# Homework_1.net
KiCad netlist of a schematic drawn in EasyEDA Pro
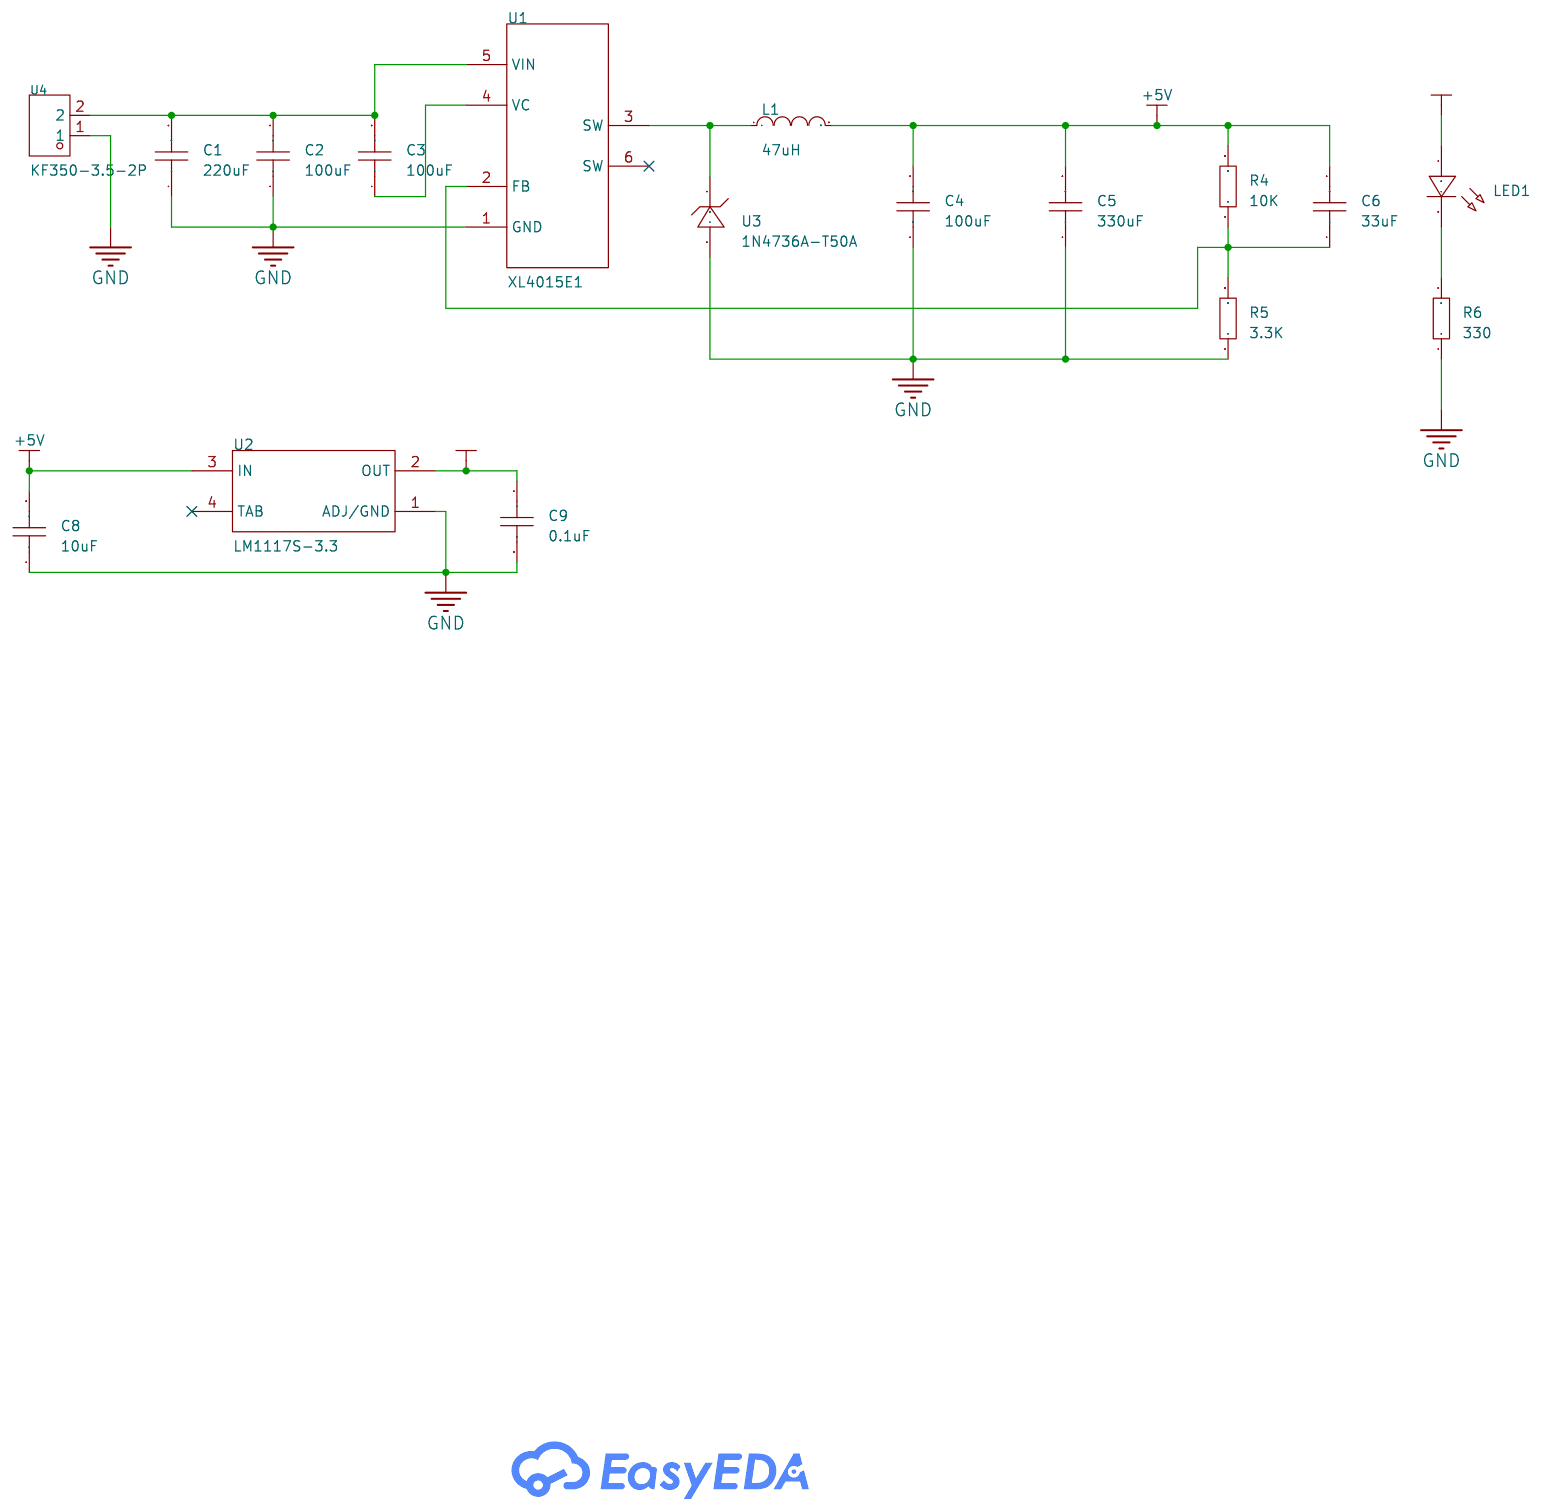
[diagram p0: Nguồn]
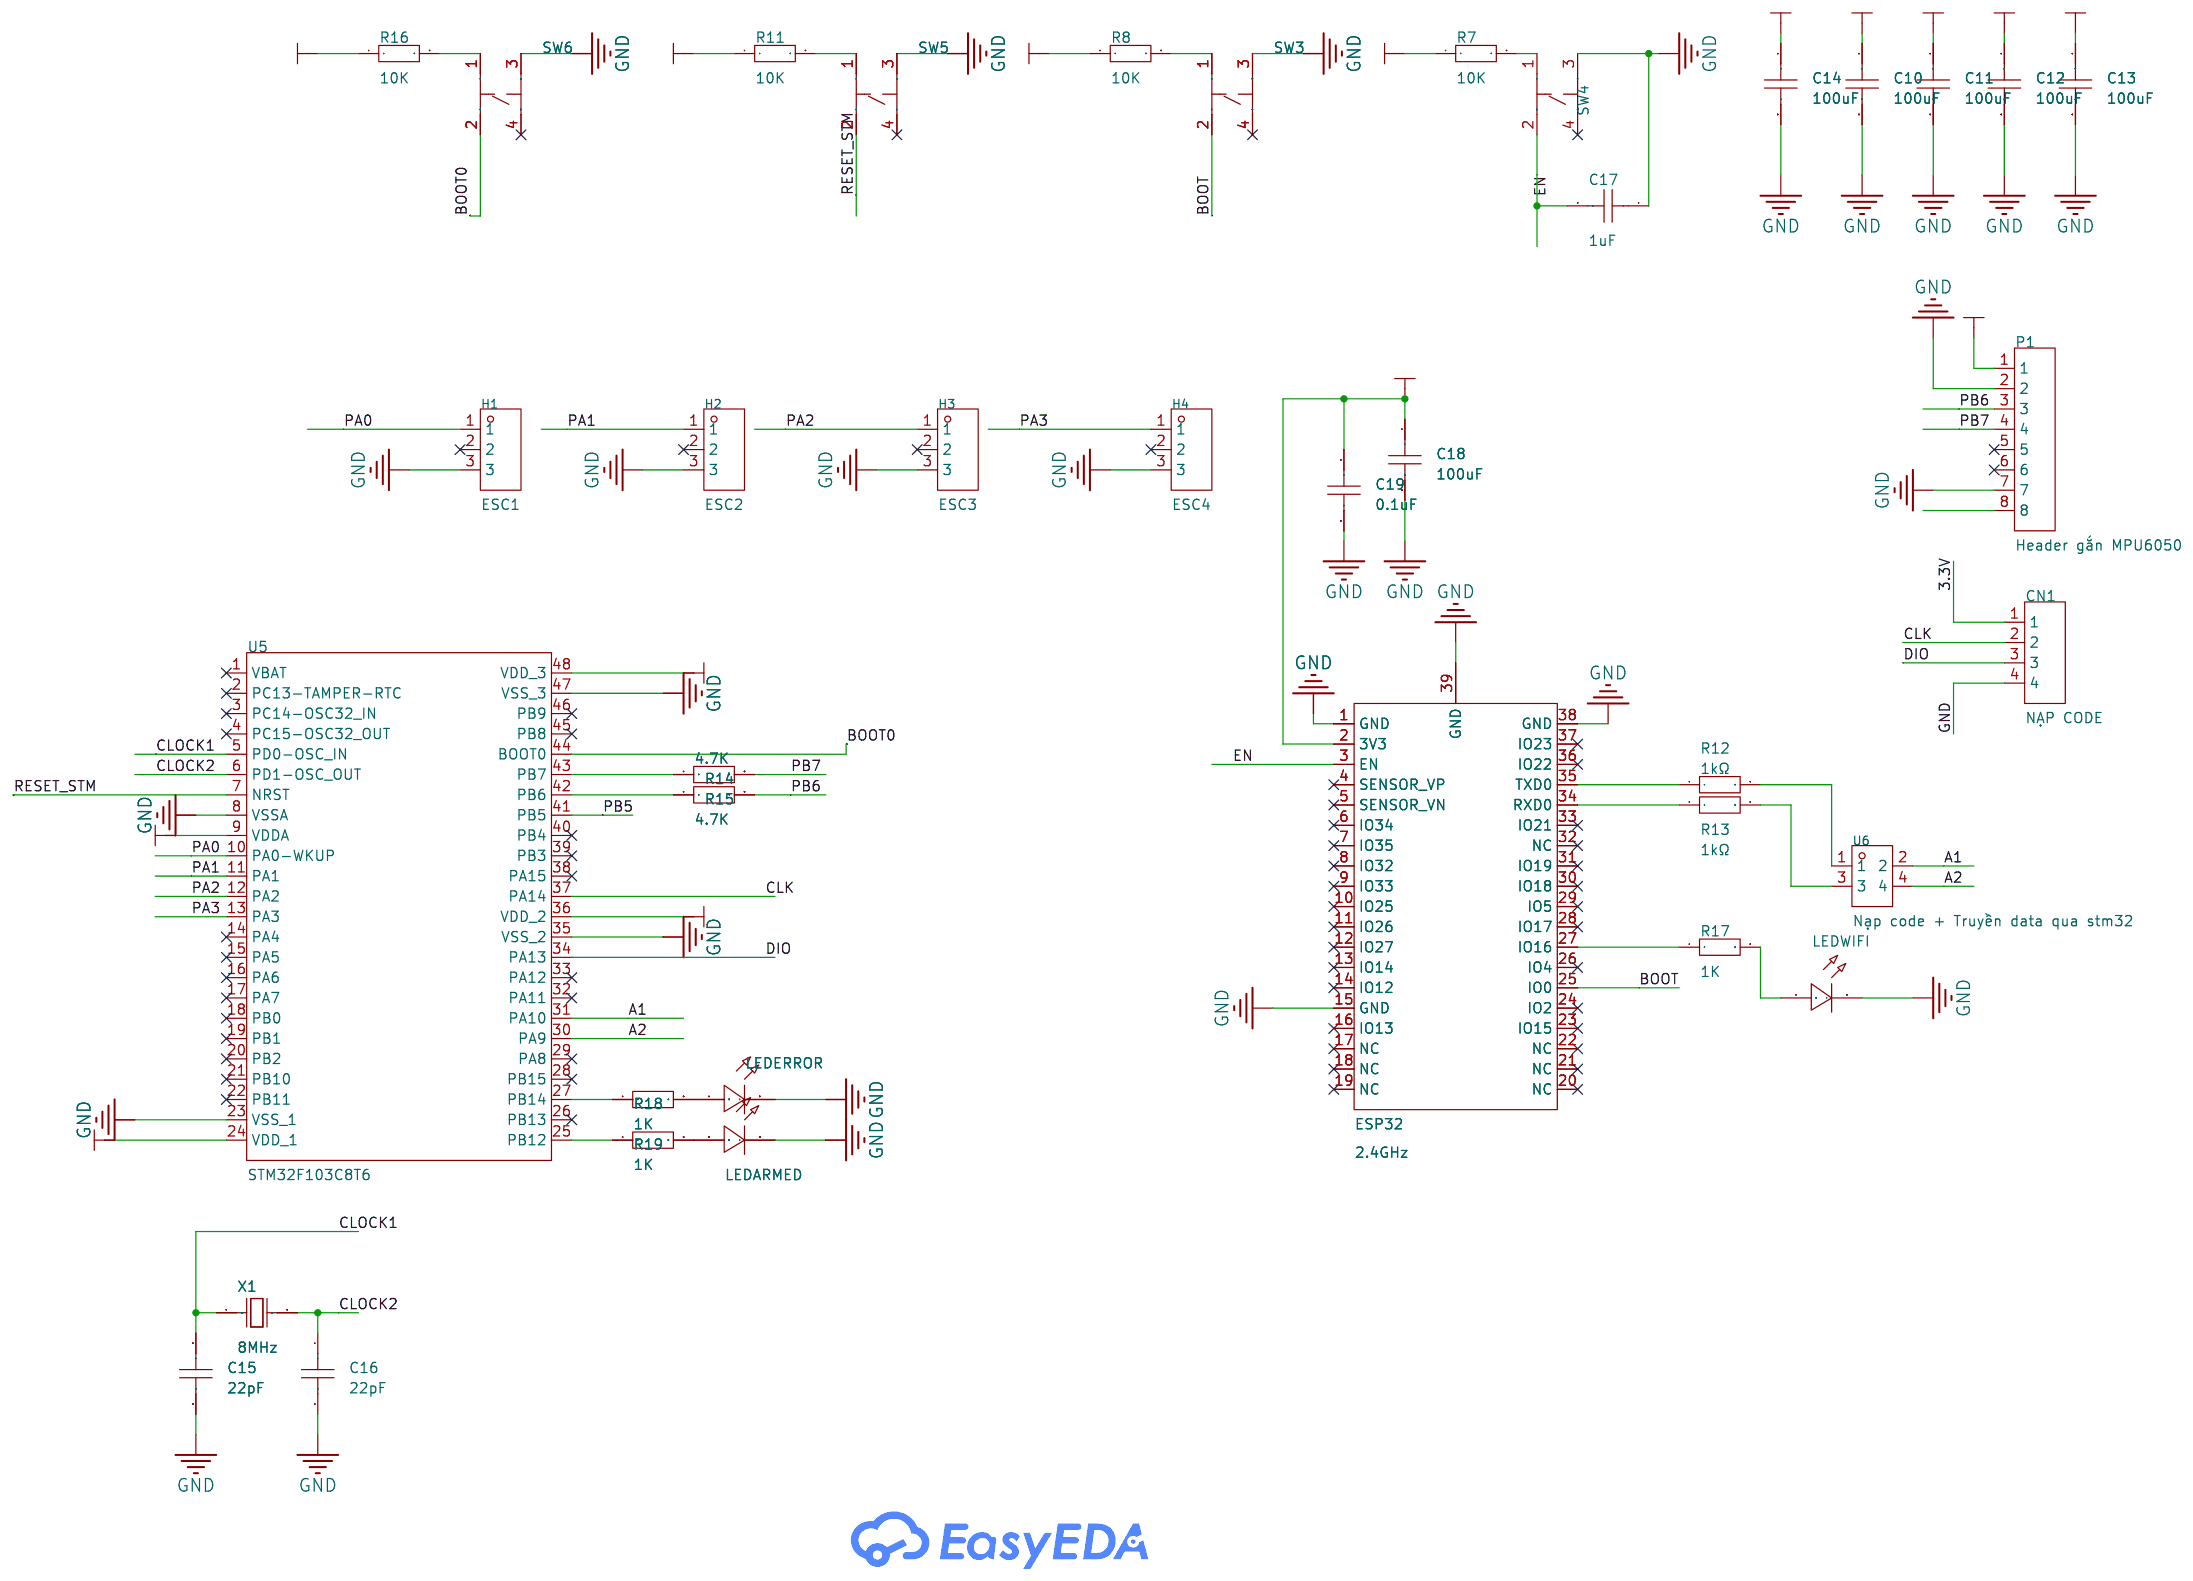
[diagram p1: Não]

(export (version "E")
  (design (tool "Eeschema 10.0.6"))
  (components
    (comp (ref "C1")
      (value "220uF")
      (footprint "easyedapro:C0805")
      (libsource (lib "easyedapro") (part "CAP"))
    )
    (comp (ref "C2")
      (value "100uF")
      (footprint "easyedapro:C0805")
      (libsource (lib "easyedapro") (part "CAP"))
    )
    (comp (ref "C3")
      (value "100uF")
      (footprint "easyedapro:C0805")
      (libsource (lib "easyedapro") (part "CAP"))
    )
    (comp (ref "C4")
      (value "100uF")
      (footprint "easyedapro:C0805")
      (libsource (lib "easyedapro") (part "CAP"))
    )
    (comp (ref "C5")
      (value "330uF")
      (footprint "easyedapro:C0805")
      (libsource (lib "easyedapro") (part "CAP"))
    )
    (comp (ref "C6")
      (value "33uF")
      (footprint "easyedapro:C0805")
      (libsource (lib "easyedapro") (part "CAP"))
    )
    (comp (ref "C8")
      (value "10uF")
      (footprint "easyedapro:C0805")
      (libsource (lib "easyedapro") (part "CAP"))
    )
    (comp (ref "C9")
      (value "0.1uF")
      (footprint "easyedapro:C0805")
      (libsource (lib "easyedapro") (part "CAP"))
    )
    (comp (ref "L1") (value "47uH") (footprint "easyedapro:L0603") (libsource (lib "easyedapro") (part "电感")))
    (comp (ref "LED1")
      (value "~")
      (footprint "easyedapro:LED-TH_BD5.8-P2.54-FD")
      (libsource (lib "easyedapro") (part "LED_TH-R"))
    )
    (comp (ref "R4")
      (value "10K")
      (footprint "easyedapro:R_AXIAL-0.4")
      (libsource (lib "easyedapro") (part "Res"))
    )
    (comp (ref "R5")
      (value "3.3K")
      (footprint "easyedapro:R_AXIAL-0.4")
      (libsource (lib "easyedapro") (part "Res"))
    )
    (comp (ref "R6")
      (value "330")
      (footprint "easyedapro:R_AXIAL-0.4")
      (libsource (lib "easyedapro") (part "Res"))
    )
    (comp (ref "U1")
      (value "XL4015E1")
      (footprint "easyedapro:TO-263-5_L10.2-W8.9-P1.70-TL")
      (fields (field (name "Manufacturer") "XLSEMI(芯龙)"))
      (libsource (lib "easyedapro") (part "XL4015E1"))
    )
    (comp (ref "U2")
      (value "LM1117S-3.3")
      (footprint "easyedapro:SOT-223-3_L6.5-W3.4-P2.30-LS7.0-BR")
      (fields (field (name "Manufacturer") "HTC"))
      (libsource (lib "easyedapro") (part "LM1117S-3.3"))
    )
    (comp (ref "U3")
      (value "1N4736A-T50A")
      (footprint "easyedapro:DO-41_BD2.4-L4.7-P8.70-D0.9-RD")
      (fields (field (name "Manufacturer") "onsemi(安森美)"))
      (libsource (lib "easyedapro") (part "1N4736A-T50A"))
    )
    (comp (ref "U4")
      (value "KF350-3.5-2P")
      (footprint "easyedapro:CONN-TH_P3.50_KF350-3.5-2P")
      (fields (field (name "Manufacturer") "KEFA(科发)"))
      (libsource (lib "easyedapro") (part "KF350-3.5-2P"))
    )
    (comp (ref "C10")
      (value "100uF")
      (footprint "easyedapro:C0805")
      (libsource (lib "easyedapro") (part "CAP"))
    )
    (comp (ref "C11")
      (value "100uF")
      (footprint "easyedapro:C0805")
      (libsource (lib "easyedapro") (part "CAP"))
    )
    (comp (ref "C12")
      (value "100uF")
      (footprint "easyedapro:C0805")
      (libsource (lib "easyedapro") (part "CAP"))
    )
    (comp (ref "C13")
      (value "100uF")
      (footprint "easyedapro:C0805")
      (libsource (lib "easyedapro") (part "CAP"))
    )
    (comp (ref "C14")
      (value "100uF")
      (footprint "easyedapro:C0805")
      (libsource (lib "easyedapro") (part "CAP"))
    )
    (comp (ref "C15")
      (value "22pF")
      (footprint "easyedapro:C0805")
      (libsource (lib "easyedapro") (part "CAP"))
    )
    (comp (ref "C16")
      (value "22pF")
      (footprint "easyedapro:C0805")
      (libsource (lib "easyedapro") (part "CAP"))
    )
    (comp (ref "C17")
      (value "1uF")
      (footprint "easyedapro:C0805")
      (libsource (lib "easyedapro") (part "CAP"))
    )
    (comp (ref "C18")
      (value "100uF")
      (footprint "easyedapro:C0805")
      (libsource (lib "easyedapro") (part "CAP"))
    )
    (comp (ref "C19")
      (value "0.1uF")
      (footprint "easyedapro:C0805")
      (libsource (lib "easyedapro") (part "CAP"))
    )
    (comp (ref "CN1")
      (value "NẠP CODE")
      (footprint "easyedapro:CONN-TH_XY-XH2.54-4A11-YT")
      (fields (field (name "Manufacturer") "HC(虹成电子)"))
      (libsource (lib "easyedapro") (part "HC-XH2.54-4A-M"))
    )
    (comp (ref "ESP32")
      (value "2.4GHz")
      (footprint "easyedapro:WIFI-SMD_ESP32-WROOM-32E")
      (fields
        (field (name "Manufacturer Part") "ESP32-WROOM-32E-N4")
        (field (name "Manufacturer") "ESPRESSIF(乐鑫)")
      )
      (libsource (lib "easyedapro") (part "ESP32-WROOM-32E(4MB)"))
    )
    (comp (ref "H1")
      (value "ESC1")
      (footprint "easyedapro:HDR-TH_3P-P2.54-V-M-1")
      (fields (field (name "Manufacturer") "ZHOURI(洲日)"))
      (libsource (lib "easyedapro") (part "2.54-1*3"))
    )
    (comp (ref "H2")
      (value "ESC2")
      (footprint "easyedapro:HDR-TH_3P-P2.54-V-M-1")
      (fields (field (name "Manufacturer") "ZHOURI(洲日)"))
      (libsource (lib "easyedapro") (part "2.54-1*3"))
    )
    (comp (ref "H3")
      (value "ESC3")
      (footprint "easyedapro:HDR-TH_3P-P2.54-V-M-1")
      (fields (field (name "Manufacturer") "ZHOURI(洲日)"))
      (libsource (lib "easyedapro") (part "2.54-1*3"))
    )
    (comp (ref "H4")
      (value "ESC4")
      (footprint "easyedapro:HDR-TH_3P-P2.54-V-M-1")
      (fields (field (name "Manufacturer") "ZHOURI(洲日)"))
      (libsource (lib "easyedapro") (part "2.54-1*3"))
    )
    (comp (ref "LEDARMED")
      (value "~")
      (footprint "easyedapro:LED-TH_BD5.8-P2.54-FD")
      (libsource (lib "easyedapro") (part "LED_TH-R"))
    )
    (comp (ref "LEDERROR")
      (value "~")
      (footprint "easyedapro:LED-TH_BD5.8-P2.54-FD")
      (libsource (lib "easyedapro") (part "LED_TH-R"))
    )
    (comp (ref "LEDWIFI")
      (value "~")
      (footprint "easyedapro:LED-TH_BD5.8-P2.54-FD")
      (libsource (lib "easyedapro") (part "LED_TH-R"))
    )
    (comp (ref "P1")
      (value "Header gắn MPU6050")
      (footprint "easyedapro:HDR-TH_8P-P2.54-V-F")
      (fields (field (name "Manufacturer") "BOOMELE(博穆精密)"))
      (libsource (lib "easyedapro") (part "Header-Female-2.54_1x8"))
    )
    (comp (ref "R7")
      (value "10K")
      (footprint "easyedapro:R_AXIAL-0.4")
      (libsource (lib "easyedapro") (part "Res"))
    )
    (comp (ref "R8")
      (value "10K")
      (footprint "easyedapro:R_AXIAL-0.4")
      (libsource (lib "easyedapro") (part "Res"))
    )
    (comp (ref "R11")
      (value "10K")
      (footprint "easyedapro:R_AXIAL-0.4")
      (libsource (lib "easyedapro") (part "Res"))
    )
    (comp (ref "R12")
      (value "1kΩ")
      (footprint "easyedapro:R_AXIAL-0.4")
      (libsource (lib "easyedapro") (part "Res"))
    )
    (comp (ref "R13")
      (value "1kΩ")
      (footprint "easyedapro:R_AXIAL-0.4")
      (libsource (lib "easyedapro") (part "Res"))
    )
    (comp (ref "R14")
      (value "4.7K")
      (footprint "easyedapro:R_AXIAL-0.4")
      (libsource (lib "easyedapro") (part "Res"))
    )
    (comp (ref "R15")
      (value "4.7K")
      (footprint "easyedapro:R_AXIAL-0.4")
      (libsource (lib "easyedapro") (part "Res"))
    )
    (comp (ref "R16")
      (value "10K")
      (footprint "easyedapro:R_AXIAL-0.4")
      (libsource (lib "easyedapro") (part "Res"))
    )
    (comp (ref "R17")
      (value "1K")
      (footprint "easyedapro:R_AXIAL-0.4")
      (libsource (lib "easyedapro") (part "Res"))
    )
    (comp (ref "R18")
      (value "1K")
      (footprint "easyedapro:R_AXIAL-0.4")
      (libsource (lib "easyedapro") (part "Res"))
    )
    (comp (ref "R19")
      (value "1K")
      (footprint "easyedapro:R_AXIAL-0.4")
      (libsource (lib "easyedapro") (part "Res"))
    )
    (comp (ref "SW3")
      (value "BOOT")
      (footprint "easyedapro:SW-SMD_4P-L6.0-W6.0-P4.50-LS9.0-H7.3")
      (fields (field (name "Manufacturer") "hanxia(韩下)"))
      (libsource (lib "easyedapro") (part "HX-6X6X7.3-TP FT SQUARE BUTTON"))
    )
    (comp (ref "SW4")
      (value "SW")
      (footprint "easyedapro:SW-SMD_4P-L6.0-W6.0-P4.50-LS9.0-H7.3")
      (fields (field (name "Manufacturer") "hanxia(韩下)"))
      (libsource (lib "easyedapro") (part "HX-6X6X7.3-TP FT SQUARE BUTTON"))
    )
    (comp (ref "SW5")
      (value "BOOT")
      (footprint "easyedapro:SW-SMD_4P-L6.0-W6.0-P4.50-LS9.0-H7.3")
      (fields (field (name "Manufacturer") "hanxia(韩下)"))
      (libsource (lib "easyedapro") (part "HX-6X6X7.3-TP FT SQUARE BUTTON"))
    )
    (comp (ref "SW6")
      (value "BOOT")
      (footprint "easyedapro:SW-SMD_4P-L6.0-W6.0-P4.50-LS9.0-H7.3")
      (fields (field (name "Manufacturer") "hanxia(韩下)"))
      (libsource (lib "easyedapro") (part "HX-6X6X7.3-TP FT SQUARE BUTTON"))
    )
    (comp (ref "U5")
      (value "STM32F103C8T6")
      (footprint "easyedapro:LQFP-48_L7.0-W7.0-P0.50-LS9.0-BL")
      (fields (field (name "Manufacturer") "ST(意法半导体)"))
      (libsource (lib "easyedapro") (part "STM32F103C8T6"))
    )
    (comp (ref "U6")
      (value "Nạp code + Truyền data qua stm32")
      (footprint "easyedapro:HDR-TH_4P-P2.54-V-M-R2-C2-S2.54")
      (fields (field (name "Manufacturer") "ZHOURI(洲日)"))
      (libsource (lib "easyedapro") (part "PZ2.54-2*2"))
    )
    (comp (ref "X1")
      (value "8MHz")
      (footprint "easyedapro:HC-49S_L11.0-W4.7-P4.88")
      (fields
        (field (name "Manufacturer Part") "049ST2-8.000F16HPNLL")
        (field (name "Manufacturer") "HCI(杭晶)")
      )
      (libsource (lib "easyedapro") (part "049ST2-8.000F16HPNLL"))
    )
  )
  (nets
    (net (code "1") (name "+5V") (class "Default")
      (node (ref "C4") (pin "2") (pinfunction "2_2") (pintype "input"))
      (node (ref "C5") (pin "2") (pinfunction "2_2") (pintype "input"))
      (node (ref "C6") (pin "2") (pinfunction "2_2") (pintype "input"))
      (node (ref "C8") (pin "2") (pinfunction "2_2") (pintype "input"))
      (node (ref "L1") (pin "2") (pinfunction "2_2") (pintype "input"))
      (node (ref "R4") (pin "2") (pinfunction "2_2") (pintype "input"))
      (node (ref "U2") (pin "3") (pinfunction "IN_3") (pintype "unspecified"))
    )
    (net (code "2") (name "3.3V") (class "Default")
      (node (ref "C10") (pin "1") (pinfunction "1_1") (pintype "input"))
      (node (ref "C11") (pin "1") (pinfunction "1_1") (pintype "input"))
      (node (ref "C12") (pin "1") (pinfunction "1_1") (pintype "input"))
      (node (ref "C13") (pin "1") (pinfunction "1_1") (pintype "input"))
      (node (ref "C14") (pin "1") (pinfunction "1_1") (pintype "input"))
      (node (ref "C18") (pin "1") (pinfunction "1_1") (pintype "input"))
      (node (ref "C19") (pin "1") (pinfunction "1_1") (pintype "input"))
      (node (ref "C9") (pin "1") (pinfunction "1_1") (pintype "input"))
      (node (ref "CN1") (pin "1") (pinfunction "1_1") (pintype "unspecified"))
      (node (ref "ESP32") (pin "2") (pinfunction "3V3_2") (pintype "unspecified"))
      (node (ref "LED1") (pin "1") (pinfunction "C_1") (pintype "input"))
      (node (ref "P1") (pin "1") (pinfunction "1_1") (pintype "unspecified"))
      (node (ref "R11") (pin "1") (pinfunction "1_1") (pintype "input"))
      (node (ref "R16") (pin "1") (pinfunction "1_1") (pintype "input"))
      (node (ref "R7") (pin "1") (pinfunction "1_1") (pintype "input"))
      (node (ref "R8") (pin "1") (pinfunction "1_1") (pintype "input"))
      (node (ref "U2") (pin "2") (pinfunction "OUT_2") (pintype "unspecified"))
      (node (ref "U5") (pin "24") (pinfunction "VDD_1_24") (pintype "unspecified"))
      (node (ref "U5") (pin "36") (pinfunction "VDD_2_36") (pintype "unspecified"))
      (node (ref "U5") (pin "48") (pinfunction "VDD_3_48") (pintype "unspecified"))
      (node (ref "U5") (pin "9") (pinfunction "VDDA_9") (pintype "unspecified"))
    )
    (net (code "3") (name "A1") (class "Default")
      (node (ref "U5") (pin "31") (pinfunction "PA10_31") (pintype "unspecified"))
      (node (ref "U6") (pin "2") (pinfunction "2_2") (pintype "input"))
    )
    (net (code "4") (name "A2") (class "Default")
      (node (ref "U5") (pin "30") (pinfunction "PA9_30") (pintype "unspecified"))
      (node (ref "U6") (pin "4") (pinfunction "4_4") (pintype "input"))
    )
    (net (code "5") (name "BOOT") (class "Default")
      (node (ref "ESP32") (pin "25") (pinfunction "IO0_25") (pintype "unspecified"))
      (node (ref "SW3") (pin "2") (pinfunction "B_2") (pintype "unspecified"))
    )
    (net (code "6") (name "BOOT0") (class "Default")
      (node (ref "SW6") (pin "2") (pinfunction "B_2") (pintype "unspecified"))
      (node (ref "U5") (pin "44") (pinfunction "BOOT0_44") (pintype "unspecified"))
    )
    (net (code "7") (name "CLK") (class "Default")
      (node (ref "CN1") (pin "2") (pinfunction "2_2") (pintype "unspecified"))
      (node (ref "U5") (pin "37") (pinfunction "PA14_37") (pintype "unspecified"))
    )
    (net (code "8") (name "CLOCK1") (class "Default")
      (node (ref "C15") (pin "1") (pinfunction "1_1") (pintype "input"))
      (node (ref "U5") (pin "5") (pinfunction "PD0-OSC_IN_5") (pintype "unspecified"))
      (node (ref "X1") (pin "1") (pinfunction "OSC1_1") (pintype "input"))
    )
    (net (code "9") (name "CLOCK2") (class "Default")
      (node (ref "C16") (pin "1") (pinfunction "1_1") (pintype "input"))
      (node (ref "U5") (pin "6") (pinfunction "PD1-OSC_OUT_6") (pintype "unspecified"))
      (node (ref "X1") (pin "2") (pinfunction "OSC2_2") (pintype "input"))
    )
    (net (code "10") (name "DIO") (class "Default")
      (node (ref "CN1") (pin "3") (pinfunction "3_3") (pintype "unspecified"))
      (node (ref "U5") (pin "34") (pinfunction "PA13_34") (pintype "unspecified"))
    )
    (net (code "11") (name "EN") (class "Default")
      (node (ref "C17") (pin "2") (pinfunction "2_2") (pintype "input"))
      (node (ref "ESP32") (pin "3") (pinfunction "EN_3") (pintype "unspecified"))
      (node (ref "SW4") (pin "2") (pinfunction "B_2") (pintype "unspecified"))
    )
    (net (code "12") (name "GND") (class "Default")
      (node (ref "C1") (pin "1") (pinfunction "1_1") (pintype "input"))
      (node (ref "C10") (pin "2") (pinfunction "2_2") (pintype "input"))
      (node (ref "C11") (pin "2") (pinfunction "2_2") (pintype "input"))
      (node (ref "C12") (pin "2") (pinfunction "2_2") (pintype "input"))
      (node (ref "C13") (pin "2") (pinfunction "2_2") (pintype "input"))
      (node (ref "C14") (pin "2") (pinfunction "2_2") (pintype "input"))
      (node (ref "C15") (pin "2") (pinfunction "2_2") (pintype "input"))
      (node (ref "C16") (pin "2") (pinfunction "2_2") (pintype "input"))
      (node (ref "C17") (pin "1") (pinfunction "1_1") (pintype "input"))
      (node (ref "C18") (pin "2") (pinfunction "2_2") (pintype "input"))
      (node (ref "C19") (pin "2") (pinfunction "2_2") (pintype "input"))
      (node (ref "C2") (pin "1") (pinfunction "1_1") (pintype "input"))
      (node (ref "C4") (pin "1") (pinfunction "1_1") (pintype "input"))
      (node (ref "C5") (pin "1") (pinfunction "1_1") (pintype "input"))
      (node (ref "C8") (pin "1") (pinfunction "1_1") (pintype "input"))
      (node (ref "C9") (pin "2") (pinfunction "2_2") (pintype "input"))
      (node (ref "CN1") (pin "4") (pinfunction "4_4") (pintype "unspecified"))
      (node (ref "ESP32") (pin "1") (pinfunction "GND_1") (pintype "unspecified"))
      (node (ref "ESP32") (pin "15") (pinfunction "GND_15") (pintype "unspecified"))
      (node (ref "ESP32") (pin "38") (pinfunction "GND_38") (pintype "unspecified"))
      (node (ref "ESP32") (pin "39") (pinfunction "GND_39") (pintype "unspecified"))
      (node (ref "H1") (pin "3") (pinfunction "3_3") (pintype "input"))
      (node (ref "H2") (pin "3") (pinfunction "3_3") (pintype "input"))
      (node (ref "H3") (pin "3") (pinfunction "3_3") (pintype "input"))
      (node (ref "H4") (pin "3") (pinfunction "3_3") (pintype "input"))
      (node (ref "LEDARMED") (pin "2") (pinfunction "A_2") (pintype "input"))
      (node (ref "LEDERROR") (pin "2") (pinfunction "A_2") (pintype "input"))
      (node (ref "LEDWIFI") (pin "2") (pinfunction "A_2") (pintype "input"))
      (node (ref "P1") (pin "2") (pinfunction "2_2") (pintype "unspecified"))
      (node (ref "P1") (pin "7") (pinfunction "7_7") (pintype "unspecified"))
      (node (ref "R5") (pin "1") (pinfunction "1_1") (pintype "input"))
      (node (ref "R6") (pin "1") (pinfunction "1_1") (pintype "input"))
      (node (ref "SW3") (pin "3") (pinfunction "C_3") (pintype "unspecified"))
      (node (ref "SW4") (pin "3") (pinfunction "C_3") (pintype "unspecified"))
      (node (ref "SW5") (pin "3") (pinfunction "C_3") (pintype "unspecified"))
      (node (ref "SW6") (pin "3") (pinfunction "C_3") (pintype "unspecified"))
      (node (ref "U1") (pin "1") (pinfunction "GND_1") (pintype "unspecified"))
      (node (ref "U2") (pin "1") (pinfunction "ADJ/GND_1") (pintype "unspecified"))
      (node (ref "U3") (pin "2") (pinfunction "A_2") (pintype "unspecified"))
      (node (ref "U4") (pin "1") (pinfunction "1_1") (pintype "input"))
      (node (ref "U5") (pin "23") (pinfunction "VSS_1_23") (pintype "unspecified"))
      (node (ref "U5") (pin "35") (pinfunction "VSS_2_35") (pintype "unspecified"))
      (node (ref "U5") (pin "47") (pinfunction "VSS_3_47") (pintype "unspecified"))
      (node (ref "U5") (pin "8") (pinfunction "VSSA_8") (pintype "unspecified"))
    )
    (net (code "13") (name "Net-(ESP32-IO16)") (class "Default")
      (node (ref "ESP32") (pin "27") (pinfunction "IO16_27") (pintype "unspecified"))
      (node (ref "R17") (pin "1") (pinfunction "1_1") (pintype "input"))
    )
    (net (code "14") (name "Net-(ESP32-RXD0)") (class "Default")
      (node (ref "ESP32") (pin "34") (pinfunction "RXD0_34") (pintype "unspecified"))
      (node (ref "R13") (pin "1") (pinfunction "1_1") (pintype "input"))
    )
    (net (code "15") (name "Net-(ESP32-TXD0)") (class "Default")
      (node (ref "ESP32") (pin "35") (pinfunction "TXD0_35") (pintype "unspecified"))
      (node (ref "R12") (pin "1") (pinfunction "1_1") (pintype "input"))
    )
    (net (code "16") (name "Net-(LED1-A)") (class "Default")
      (node (ref "LED1") (pin "2") (pinfunction "A_2") (pintype "input"))
      (node (ref "R6") (pin "2") (pinfunction "2_2") (pintype "input"))
    )
    (net (code "17") (name "Net-(LEDARMED-C)") (class "Default")
      (node (ref "LEDARMED") (pin "1") (pinfunction "C_1") (pintype "input"))
      (node (ref "R19") (pin "2") (pinfunction "2_2") (pintype "input"))
    )
    (net (code "18") (name "Net-(LEDERROR-C)") (class "Default")
      (node (ref "LEDERROR") (pin "1") (pinfunction "C_1") (pintype "input"))
      (node (ref "R18") (pin "2") (pinfunction "2_2") (pintype "input"))
    )
    (net (code "19") (name "Net-(LEDWIFI-C)") (class "Default")
      (node (ref "LEDWIFI") (pin "1") (pinfunction "C_1") (pintype "input"))
      (node (ref "R17") (pin "2") (pinfunction "2_2") (pintype "input"))
    )
    (net (code "20") (name "Net-(R12-Pad2)") (class "Default")
      (node (ref "R12") (pin "2") (pinfunction "2_2") (pintype "input"))
      (node (ref "U6") (pin "1") (pinfunction "1_1") (pintype "input"))
    )
    (net (code "21") (name "Net-(R13-Pad2)") (class "Default")
      (node (ref "R13") (pin "2") (pinfunction "2_2") (pintype "input"))
      (node (ref "U6") (pin "3") (pinfunction "3_3") (pintype "input"))
    )
    (net (code "22") (name "Net-(SW3-A)") (class "Default")
      (node (ref "R8") (pin "2") (pinfunction "2_2") (pintype "input"))
      (node (ref "SW3") (pin "1") (pinfunction "A_1") (pintype "unspecified"))
    )
    (net (code "23") (name "Net-(SW4-A)") (class "Default")
      (node (ref "R7") (pin "2") (pinfunction "2_2") (pintype "input"))
      (node (ref "SW4") (pin "1") (pinfunction "A_1") (pintype "unspecified"))
    )
    (net (code "24") (name "Net-(SW5-A)") (class "Default")
      (node (ref "R11") (pin "2") (pinfunction "2_2") (pintype "input"))
      (node (ref "SW5") (pin "1") (pinfunction "A_1") (pintype "unspecified"))
    )
    (net (code "25") (name "Net-(SW6-A)") (class "Default")
      (node (ref "R16") (pin "2") (pinfunction "2_2") (pintype "input"))
      (node (ref "SW6") (pin "1") (pinfunction "A_1") (pintype "unspecified"))
    )
    (net (code "26") (name "Net-(U1-FB)") (class "Default")
      (node (ref "C6") (pin "1") (pinfunction "1_1") (pintype "input"))
      (node (ref "R4") (pin "1") (pinfunction "1_1") (pintype "input"))
      (node (ref "R5") (pin "2") (pinfunction "2_2") (pintype "input"))
      (node (ref "U1") (pin "2") (pinfunction "FB_2") (pintype "unspecified"))
    )
    (net (code "27") (name "Net-(U1-VC)") (class "Default")
      (node (ref "C3") (pin "1") (pinfunction "1_1") (pintype "input"))
      (node (ref "U1") (pin "4") (pinfunction "VC_4") (pintype "unspecified"))
    )
    (net (code "28") (name "Net-(U1-VIN)") (class "Default")
      (node (ref "C1") (pin "2") (pinfunction "2_2") (pintype "input"))
      (node (ref "C2") (pin "2") (pinfunction "2_2") (pintype "input"))
      (node (ref "C3") (pin "2") (pinfunction "2_2") (pintype "input"))
      (node (ref "U1") (pin "5") (pinfunction "VIN_5") (pintype "unspecified"))
      (node (ref "U4") (pin "2") (pinfunction "2_2") (pintype "input"))
    )
    (net (code "29") (name "Net-(U3-C)") (class "Default")
      (node (ref "L1") (pin "1") (pinfunction "1_1") (pintype "input"))
      (node (ref "U1") (pin "3") (pinfunction "SW_3") (pintype "unspecified"))
      (node (ref "U3") (pin "1") (pinfunction "C_1") (pintype "unspecified"))
    )
    (net (code "30") (name "Net-(U5-PB6)") (class "Default")
      (node (ref "R15") (pin "1") (pinfunction "1_1") (pintype "input"))
      (node (ref "U5") (pin "42") (pinfunction "PB6_42") (pintype "unspecified"))
    )
    (net (code "31") (name "Net-(U5-PB7)") (class "Default")
      (node (ref "R14") (pin "1") (pinfunction "1_1") (pintype "input"))
      (node (ref "U5") (pin "43") (pinfunction "PB7_43") (pintype "unspecified"))
    )
    (net (code "32") (name "Net-(U5-PB12)") (class "Default")
      (node (ref "R19") (pin "1") (pinfunction "1_1") (pintype "input"))
      (node (ref "U5") (pin "25") (pinfunction "PB12_25") (pintype "unspecified"))
    )
    (net (code "33") (name "Net-(U5-PB14)") (class "Default")
      (node (ref "R18") (pin "1") (pinfunction "1_1") (pintype "input"))
      (node (ref "U5") (pin "27") (pinfunction "PB14_27") (pintype "unspecified"))
    )
    (net (code "34") (name "PA0") (class "Default")
      (node (ref "H1") (pin "1") (pinfunction "1_1") (pintype "input"))
      (node (ref "U5") (pin "10") (pinfunction "PA0-WKUP_10") (pintype "unspecified"))
    )
    (net (code "35") (name "PA1") (class "Default")
      (node (ref "H2") (pin "1") (pinfunction "1_1") (pintype "input"))
      (node (ref "U5") (pin "11") (pinfunction "PA1_11") (pintype "unspecified"))
    )
    (net (code "36") (name "PA2") (class "Default")
      (node (ref "H3") (pin "1") (pinfunction "1_1") (pintype "input"))
      (node (ref "U5") (pin "12") (pinfunction "PA2_12") (pintype "unspecified"))
    )
    (net (code "37") (name "PA3") (class "Default")
      (node (ref "H4") (pin "1") (pinfunction "1_1") (pintype "input"))
      (node (ref "U5") (pin "13") (pinfunction "PA3_13") (pintype "unspecified"))
    )
    (net (code "38") (name "PB5") (class "Default")
      (node (ref "U5") (pin "41") (pinfunction "PB5_41") (pintype "unspecified"))
    )
    (net (code "39") (name "PB6") (class "Default")
      (node (ref "P1") (pin "3") (pinfunction "3_3") (pintype "unspecified"))
      (node (ref "R15") (pin "2") (pinfunction "2_2") (pintype "input"))
    )
    (net (code "40") (name "PB7") (class "Default")
      (node (ref "P1") (pin "4") (pinfunction "4_4") (pintype "unspecified"))
      (node (ref "R14") (pin "2") (pinfunction "2_2") (pintype "input"))
    )
    (net (code "41") (name "RESET_STM") (class "Default")
      (node (ref "SW5") (pin "2") (pinfunction "B_2") (pintype "unspecified"))
      (node (ref "U5") (pin "7") (pinfunction "NRST_7") (pintype "unspecified"))
    )
    (net (code "42") (name "unconnected-(ESP32-IO2-Pad24)") (class "Default")
      (node (ref "ESP32") (pin "24") (pinfunction "IO2_24") (pintype "unspecified+no_connect"))
    )
    (net (code "43") (name "unconnected-(ESP32-IO4-Pad26)") (class "Default")
      (node (ref "ESP32") (pin "26") (pinfunction "IO4_26") (pintype "unspecified+no_connect"))
    )
    (net (code "44") (name "unconnected-(ESP32-IO5-Pad29)") (class "Default")
      (node (ref "ESP32") (pin "29") (pinfunction "IO5_29") (pintype "unspecified+no_connect"))
    )
    (net (code "45") (name "unconnected-(ESP32-IO12-Pad14)") (class "Default")
      (node (ref "ESP32") (pin "14") (pinfunction "IO12_14") (pintype "unspecified+no_connect"))
    )
    (net (code "46") (name "unconnected-(ESP32-IO13-Pad16)") (class "Default")
      (node (ref "ESP32") (pin "16") (pinfunction "IO13_16") (pintype "unspecified+no_connect"))
    )
    (net (code "47") (name "unconnected-(ESP32-IO14-Pad13)") (class "Default")
      (node (ref "ESP32") (pin "13") (pinfunction "IO14_13") (pintype "unspecified+no_connect"))
    )
    (net (code "48") (name "unconnected-(ESP32-IO15-Pad23)") (class "Default")
      (node (ref "ESP32") (pin "23") (pinfunction "IO15_23") (pintype "unspecified+no_connect"))
    )
    (net (code "49") (name "unconnected-(ESP32-IO17-Pad28)") (class "Default")
      (node (ref "ESP32") (pin "28") (pinfunction "IO17_28") (pintype "unspecified+no_connect"))
    )
    (net (code "50") (name "unconnected-(ESP32-IO18-Pad30)") (class "Default")
      (node (ref "ESP32") (pin "30") (pinfunction "IO18_30") (pintype "unspecified+no_connect"))
    )
    (net (code "51") (name "unconnected-(ESP32-IO19-Pad31)") (class "Default")
      (node (ref "ESP32") (pin "31") (pinfunction "IO19_31") (pintype "unspecified+no_connect"))
    )
    (net (code "52") (name "unconnected-(ESP32-IO21-Pad33)") (class "Default")
      (node (ref "ESP32") (pin "33") (pinfunction "IO21_33") (pintype "unspecified+no_connect"))
    )
    (net (code "53") (name "unconnected-(ESP32-IO22-Pad36)") (class "Default")
      (node (ref "ESP32") (pin "36") (pinfunction "IO22_36") (pintype "unspecified+no_connect"))
    )
    (net (code "54") (name "unconnected-(ESP32-IO23-Pad37)") (class "Default")
      (node (ref "ESP32") (pin "37") (pinfunction "IO23_37") (pintype "unspecified+no_connect"))
    )
    (net (code "55") (name "unconnected-(ESP32-IO25-Pad10)") (class "Default")
      (node (ref "ESP32") (pin "10") (pinfunction "IO25_10") (pintype "unspecified+no_connect"))
    )
    (net (code "56") (name "unconnected-(ESP32-IO26-Pad11)") (class "Default")
      (node (ref "ESP32") (pin "11") (pinfunction "IO26_11") (pintype "unspecified+no_connect"))
    )
    (net (code "57") (name "unconnected-(ESP32-IO27-Pad12)") (class "Default")
      (node (ref "ESP32") (pin "12") (pinfunction "IO27_12") (pintype "unspecified+no_connect"))
    )
    (net (code "58") (name "unconnected-(ESP32-IO32-Pad8)") (class "Default")
      (node (ref "ESP32") (pin "8") (pinfunction "IO32_8") (pintype "unspecified+no_connect"))
    )
    (net (code "59") (name "unconnected-(ESP32-IO33-Pad9)") (class "Default")
      (node (ref "ESP32") (pin "9") (pinfunction "IO33_9") (pintype "unspecified+no_connect"))
    )
    (net (code "60") (name "unconnected-(ESP32-IO34-Pad6)") (class "Default")
      (node (ref "ESP32") (pin "6") (pinfunction "IO34_6") (pintype "unspecified+no_connect"))
    )
    (net (code "61") (name "unconnected-(ESP32-IO35-Pad7)") (class "Default")
      (node (ref "ESP32") (pin "7") (pinfunction "IO35_7") (pintype "unspecified+no_connect"))
    )
    (net (code "62") (name "unconnected-(ESP32-NC-Pad17)") (class "Default")
      (node (ref "ESP32") (pin "17") (pinfunction "NC_17") (pintype "unspecified+no_connect"))
    )
    (net (code "63") (name "unconnected-(ESP32-NC-Pad18)") (class "Default")
      (node (ref "ESP32") (pin "18") (pinfunction "NC_18") (pintype "unspecified+no_connect"))
    )
    (net (code "64") (name "unconnected-(ESP32-NC-Pad19)") (class "Default")
      (node (ref "ESP32") (pin "19") (pinfunction "NC_19") (pintype "unspecified+no_connect"))
    )
    (net (code "65") (name "unconnected-(ESP32-NC-Pad20)") (class "Default")
      (node (ref "ESP32") (pin "20") (pinfunction "NC_20") (pintype "unspecified+no_connect"))
    )
    (net (code "66") (name "unconnected-(ESP32-NC-Pad21)") (class "Default")
      (node (ref "ESP32") (pin "21") (pinfunction "NC_21") (pintype "unspecified+no_connect"))
    )
    (net (code "67") (name "unconnected-(ESP32-NC-Pad22)") (class "Default")
      (node (ref "ESP32") (pin "22") (pinfunction "NC_22") (pintype "unspecified+no_connect"))
    )
    (net (code "68") (name "unconnected-(ESP32-NC-Pad32)") (class "Default")
      (node (ref "ESP32") (pin "32") (pinfunction "NC_32") (pintype "unspecified+no_connect"))
    )
    (net (code "69") (name "unconnected-(ESP32-SENSOR_VN-Pad5)") (class "Default")
      (node (ref "ESP32") (pin "5") (pinfunction "SENSOR_VN_5") (pintype "unspecified+no_connect"))
    )
    (net (code "70") (name "unconnected-(ESP32-SENSOR_VP-Pad4)") (class "Default")
      (node (ref "ESP32") (pin "4") (pinfunction "SENSOR_VP_4") (pintype "unspecified+no_connect"))
    )
    (net (code "71") (name "unconnected-(H1-Pad2)") (class "Default")
      (node (ref "H1") (pin "2") (pinfunction "2_2") (pintype "input+no_connect"))
    )
    (net (code "72") (name "unconnected-(H2-Pad2)") (class "Default")
      (node (ref "H2") (pin "2") (pinfunction "2_2") (pintype "input+no_connect"))
    )
    (net (code "73") (name "unconnected-(H3-Pad2)") (class "Default")
      (node (ref "H3") (pin "2") (pinfunction "2_2") (pintype "input+no_connect"))
    )
    (net (code "74") (name "unconnected-(H4-Pad2)") (class "Default")
      (node (ref "H4") (pin "2") (pinfunction "2_2") (pintype "input+no_connect"))
    )
    (net (code "75") (name "unconnected-(P1-Pad5)") (class "Default")
      (node (ref "P1") (pin "5") (pinfunction "5_5") (pintype "unspecified+no_connect"))
    )
    (net (code "76") (name "unconnected-(P1-Pad6)") (class "Default")
      (node (ref "P1") (pin "6") (pinfunction "6_6") (pintype "unspecified+no_connect"))
    )
    (net (code "77") (name "unconnected-(P1-Pad8)") (class "Default")
      (node (ref "P1") (pin "8") (pinfunction "8_8") (pintype "unspecified"))
    )
    (net (code "78") (name "unconnected-(SW3-D-Pad4)") (class "Default")
      (node (ref "SW3") (pin "4") (pinfunction "D_4") (pintype "unspecified+no_connect"))
    )
    (net (code "79") (name "unconnected-(SW4-D-Pad4)") (class "Default")
      (node (ref "SW4") (pin "4") (pinfunction "D_4") (pintype "unspecified+no_connect"))
    )
    (net (code "80") (name "unconnected-(SW5-D-Pad4)") (class "Default")
      (node (ref "SW5") (pin "4") (pinfunction "D_4") (pintype "unspecified+no_connect"))
    )
    (net (code "81") (name "unconnected-(SW6-D-Pad4)") (class "Default")
      (node (ref "SW6") (pin "4") (pinfunction "D_4") (pintype "unspecified+no_connect"))
    )
    (net (code "82") (name "unconnected-(U1-SW-Pad6)") (class "Default")
      (node (ref "U1") (pin "6") (pinfunction "SW_6") (pintype "unspecified+no_connect"))
    )
    (net (code "83") (name "unconnected-(U2-TAB-Pad4)") (class "Default")
      (node (ref "U2") (pin "4") (pinfunction "TAB_4") (pintype "unspecified+no_connect"))
    )
    (net (code "84") (name "unconnected-(U5-PA4-Pad14)") (class "Default")
      (node (ref "U5") (pin "14") (pinfunction "PA4_14") (pintype "unspecified+no_connect"))
    )
    (net (code "85") (name "unconnected-(U5-PA5-Pad15)") (class "Default")
      (node (ref "U5") (pin "15") (pinfunction "PA5_15") (pintype "unspecified+no_connect"))
    )
    (net (code "86") (name "unconnected-(U5-PA6-Pad16)") (class "Default")
      (node (ref "U5") (pin "16") (pinfunction "PA6_16") (pintype "unspecified+no_connect"))
    )
    (net (code "87") (name "unconnected-(U5-PA7-Pad17)") (class "Default")
      (node (ref "U5") (pin "17") (pinfunction "PA7_17") (pintype "unspecified+no_connect"))
    )
    (net (code "88") (name "unconnected-(U5-PA8-Pad29)") (class "Default")
      (node (ref "U5") (pin "29") (pinfunction "PA8_29") (pintype "unspecified+no_connect"))
    )
    (net (code "89") (name "unconnected-(U5-PA11-Pad32)") (class "Default")
      (node (ref "U5") (pin "32") (pinfunction "PA11_32") (pintype "unspecified+no_connect"))
    )
    (net (code "90") (name "unconnected-(U5-PA12-Pad33)") (class "Default")
      (node (ref "U5") (pin "33") (pinfunction "PA12_33") (pintype "unspecified+no_connect"))
    )
    (net (code "91") (name "unconnected-(U5-PA15-Pad38)") (class "Default")
      (node (ref "U5") (pin "38") (pinfunction "PA15_38") (pintype "unspecified+no_connect"))
    )
    (net (code "92") (name "unconnected-(U5-PB0-Pad18)") (class "Default")
      (node (ref "U5") (pin "18") (pinfunction "PB0_18") (pintype "unspecified+no_connect"))
    )
    (net (code "93") (name "unconnected-(U5-PB1-Pad19)") (class "Default")
      (node (ref "U5") (pin "19") (pinfunction "PB1_19") (pintype "unspecified+no_connect"))
    )
    (net (code "94") (name "unconnected-(U5-PB2-Pad20)") (class "Default")
      (node (ref "U5") (pin "20") (pinfunction "PB2_20") (pintype "unspecified+no_connect"))
    )
    (net (code "95") (name "unconnected-(U5-PB3-Pad39)") (class "Default")
      (node (ref "U5") (pin "39") (pinfunction "PB3_39") (pintype "unspecified+no_connect"))
    )
    (net (code "96") (name "unconnected-(U5-PB4-Pad40)") (class "Default")
      (node (ref "U5") (pin "40") (pinfunction "PB4_40") (pintype "unspecified+no_connect"))
    )
    (net (code "97") (name "unconnected-(U5-PB8-Pad45)") (class "Default")
      (node (ref "U5") (pin "45") (pinfunction "PB8_45") (pintype "unspecified+no_connect"))
    )
    (net (code "98") (name "unconnected-(U5-PB9-Pad46)") (class "Default")
      (node (ref "U5") (pin "46") (pinfunction "PB9_46") (pintype "unspecified+no_connect"))
    )
    (net (code "99") (name "unconnected-(U5-PB10-Pad21)") (class "Default")
      (node (ref "U5") (pin "21") (pinfunction "PB10_21") (pintype "unspecified+no_connect"))
    )
    (net (code "100") (name "unconnected-(U5-PB11-Pad22)") (class "Default")
      (node (ref "U5") (pin "22") (pinfunction "PB11_22") (pintype "unspecified+no_connect"))
    )
    (net (code "101") (name "unconnected-(U5-PB13-Pad26)") (class "Default")
      (node (ref "U5") (pin "26") (pinfunction "PB13_26") (pintype "unspecified+no_connect"))
    )
    (net (code "102") (name "unconnected-(U5-PB15-Pad28)") (class "Default")
      (node (ref "U5") (pin "28") (pinfunction "PB15_28") (pintype "unspecified+no_connect"))
    )
    (net (code "103") (name "unconnected-(U5-PC13-TAMPER-RTC-Pad2)") (class "Default")
      (node (ref "U5") (pin "2") (pinfunction "PC13-TAMPER-RTC_2") (pintype "unspecified+no_connect"))
    )
    (net (code "104") (name "unconnected-(U5-PC14-OSC32_IN-Pad3)") (class "Default")
      (node (ref "U5") (pin "3") (pinfunction "PC14-OSC32_IN_3") (pintype "unspecified+no_connect"))
    )
    (net (code "105") (name "unconnected-(U5-PC15-OSC32_OUT-Pad4)") (class "Default")
      (node (ref "U5") (pin "4") (pinfunction "PC15-OSC32_OUT_4") (pintype "unspecified+no_connect"))
    )
    (net (code "106") (name "unconnected-(U5-VBAT-Pad1)") (class "Default")
      (node (ref "U5") (pin "1") (pinfunction "VBAT_1") (pintype "unspecified+no_connect"))
    )
  )
)
